# Ext_Components.net
KiCad netlist of a schematic drawn in Altium Designer
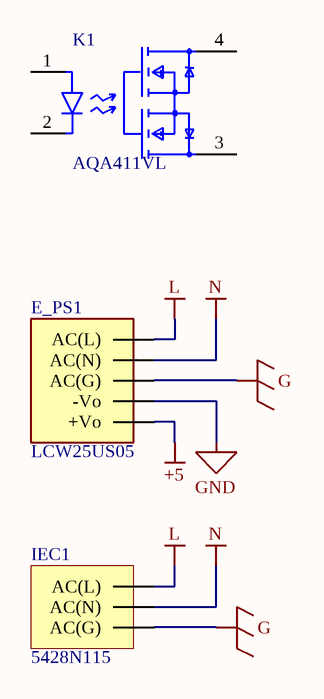
[diagram p0: Ext_Components.SchDoc]

(export (version "E")
  (design (tool "Eeschema 10.0.6"))
  (components
    (comp (ref "E_PS1")
      (value "LCW25US05")
      (footprint "LCW25US12-Footprint-1")
      (description "Power Supply, AC-DC, Enclosed, Industrial, 25W, 5V, LCW25 Series")
      (libsource (lib "IIT Motorsports") (part "9bfe63f1ac6509a30e43ee188490ecc"))
    )
    (comp (ref "IEC1")
      (value "5428N115")
      (footprint "5428N115-Footprint-1")
      (description "IEC Connector with Power Switch Screw on, C20, 20A UL, DPST-NO")
      (libsource (lib "IIT Motorsports") (part "5428N115-Symbol-1"))
    )
    (comp (ref "K1")
      (value "AQA411VL")
      (footprint "AQA411VL-Footprint-1")
      (description "Relay Ssr 50MA 1.5V Dc-in 0.25A 40V Ac/dc-out 4-PIN SSOP T/r")
      (libsource (lib "IIT Motorsports") (part "39108d2c2fe9c6c4263f1aa8ae40286"))
    )
  )
  (nets
    (net (code "1") (name "+5") (class "Default")
      (node (ref "E_PS1") (pin "4") (pinfunction "+Vo_4") (pintype "passive"))
    )
    (net (code "2") (name "G") (class "Default")
      (node (ref "E_PS1") (pin "2") (pinfunction "AC(G)_2") (pintype "passive"))
      (node (ref "IEC1") (pin "2") (pinfunction "AC(G)_2") (pintype "passive"))
    )
    (net (code "3") (name "GND") (class "Default")
      (node (ref "E_PS1") (pin "3") (pinfunction "-Vo_3") (pintype "passive"))
    )
    (net (code "4") (name "L") (class "Default")
      (node (ref "E_PS1") (pin "0") (pinfunction "AC(L)_0") (pintype "passive"))
      (node (ref "IEC1") (pin "0") (pinfunction "AC(L)_0") (pintype "passive"))
    )
    (net (code "5") (name "N") (class "Default")
      (node (ref "E_PS1") (pin "1") (pinfunction "AC(N)_1") (pintype "passive"))
      (node (ref "IEC1") (pin "1") (pinfunction "AC(N)_1") (pintype "passive"))
    )
    (net (code "6") (name "unconnected-(K1-1_DRAIN-Pad3)") (class "Default")
      (node (ref "K1") (pin "3") (pinfunction "1_DRAIN_3") (pintype "passive"))
    )
    (net (code "7") (name "unconnected-(K1-2_DRAIN-Pad4)") (class "Default")
      (node (ref "K1") (pin "4") (pinfunction "2_DRAIN_4") (pintype "passive"))
    )
    (net (code "8") (name "unconnected-(K1-A-Pad1)") (class "Default")
      (node (ref "K1") (pin "1") (pinfunction "A_1") (pintype "passive"))
    )
    (net (code "9") (name "unconnected-(K1-C-Pad2)") (class "Default")
      (node (ref "K1") (pin "2") (pinfunction "C_2") (pintype "passive"))
    )
  )
)
